# design.net
KiCad netlist of a schematic drawn in EasyEDA Pro
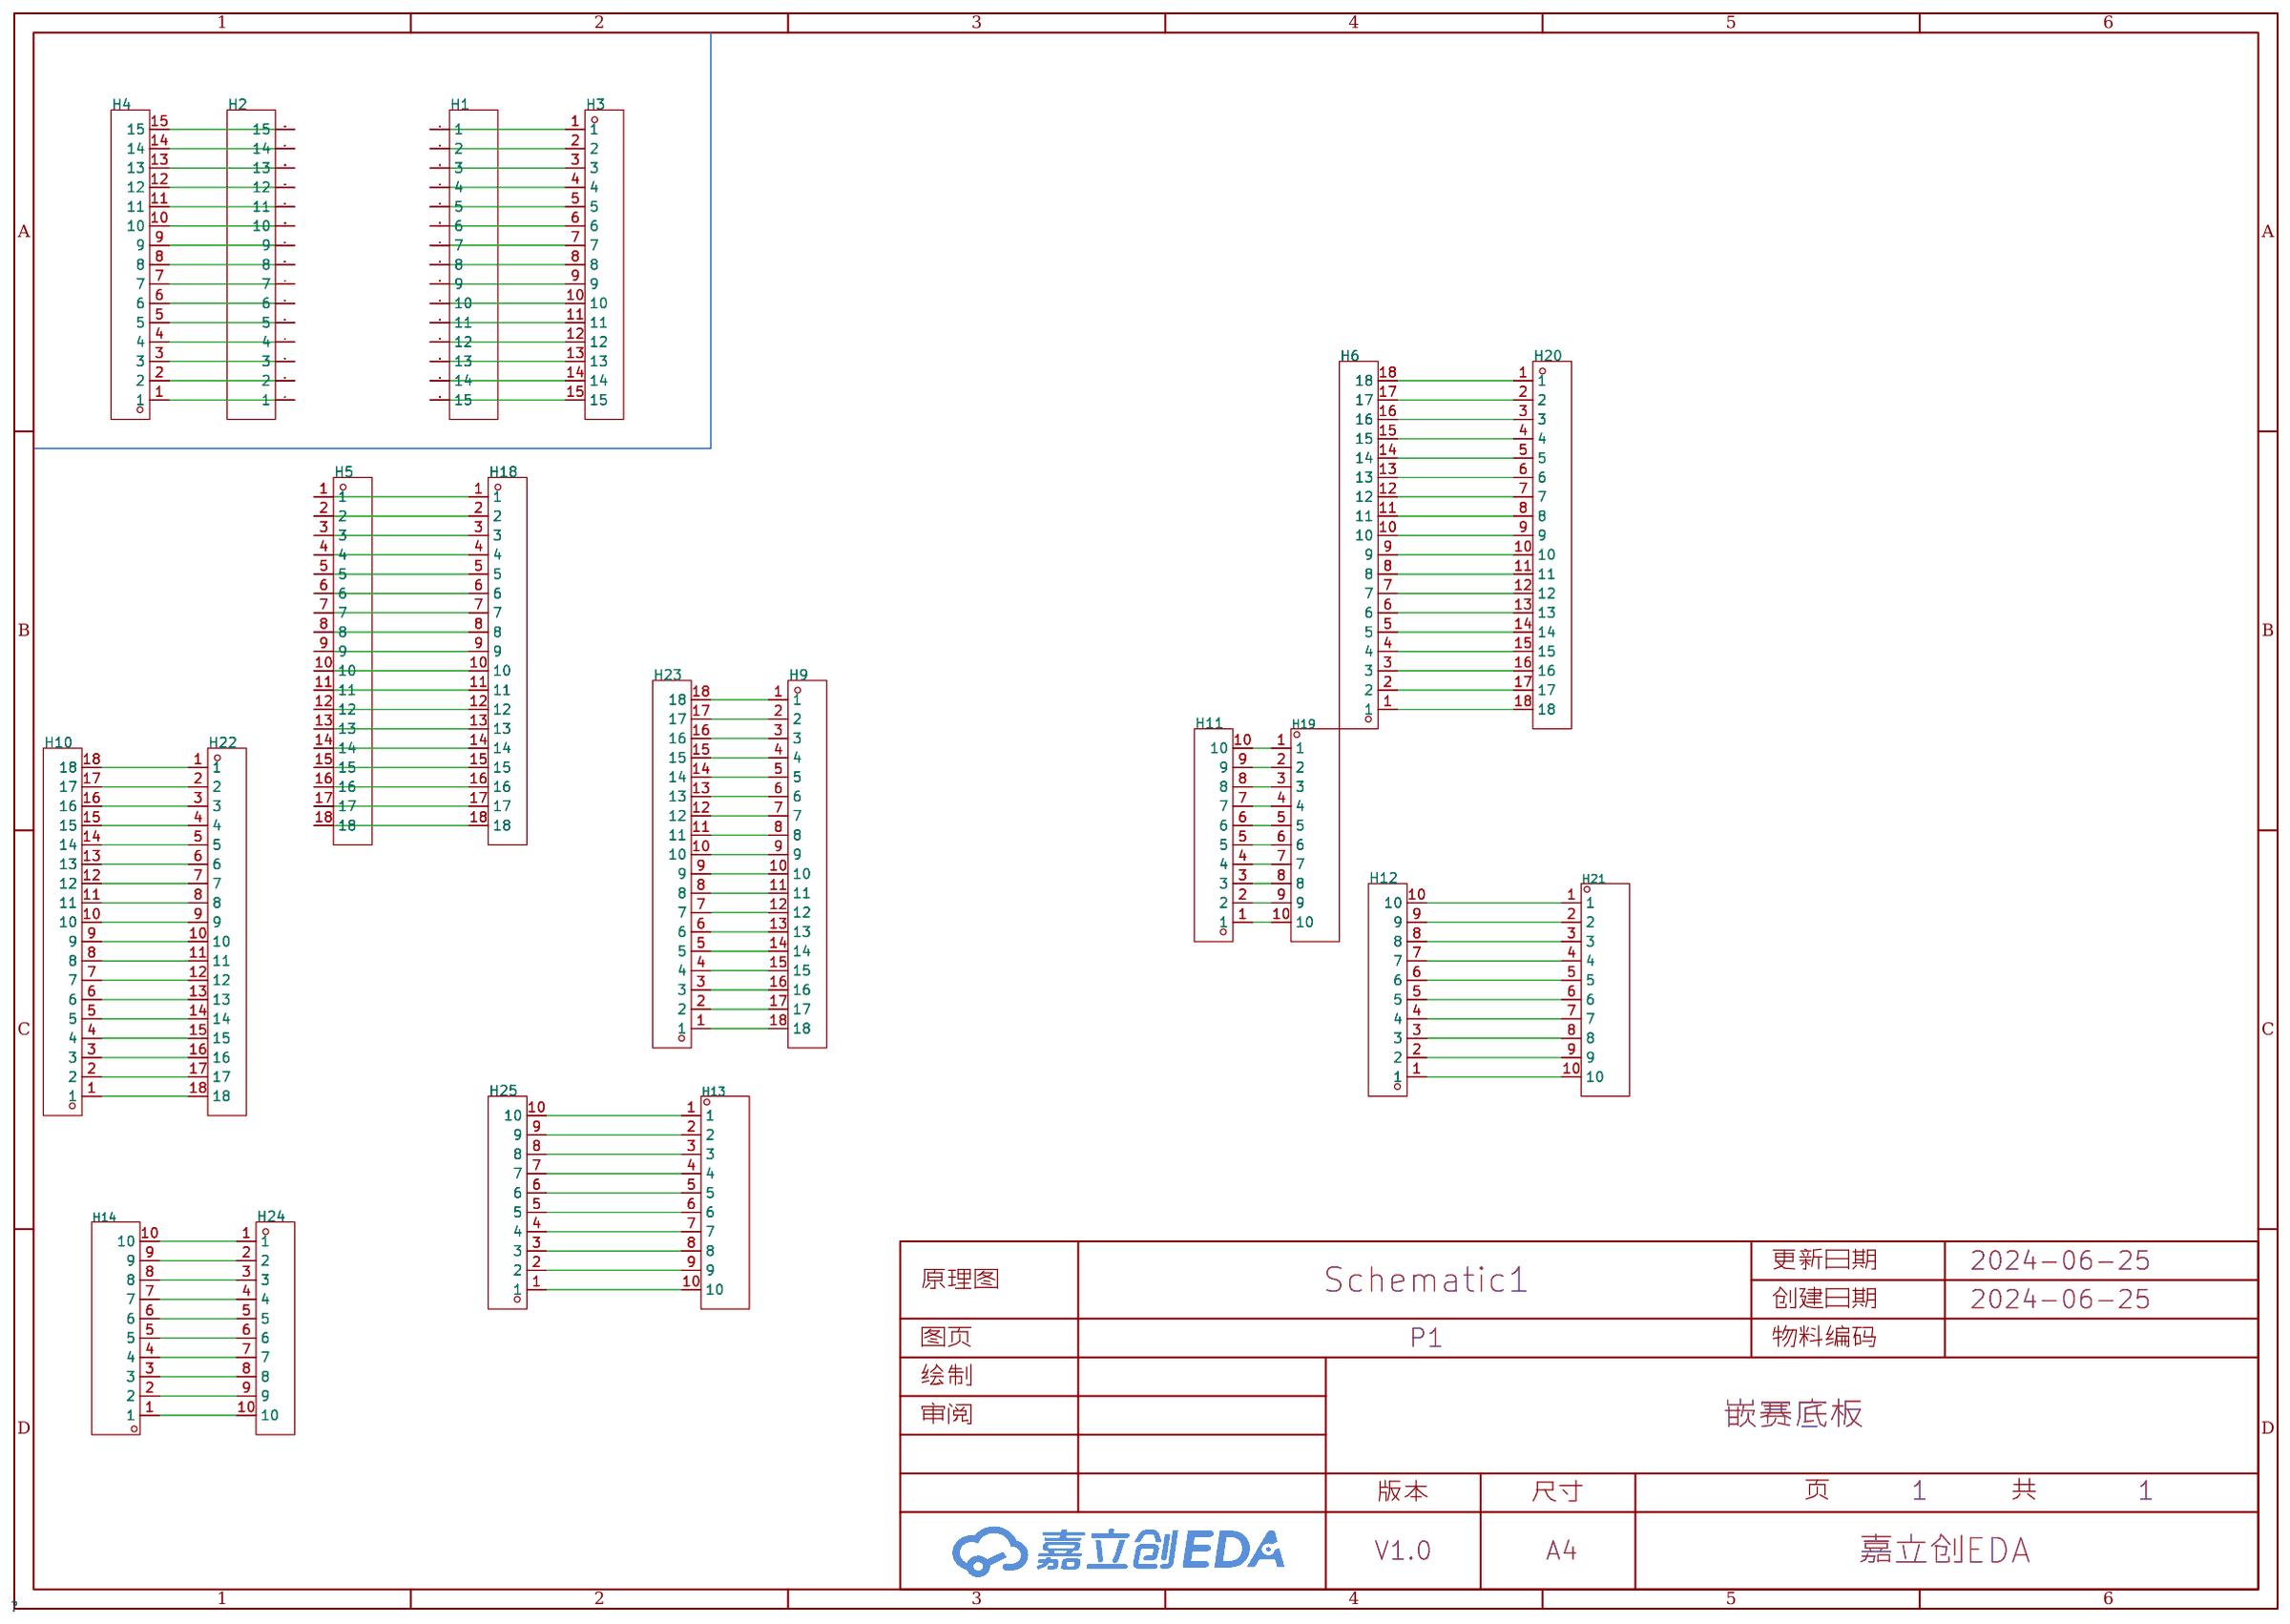
[diagram p0: schematic sheet]

(export (version "E")
  (design (tool "Eeschema 10.0.6"))
  (components
    (comp (ref "H1")
      (value "~")
      (footprint "easyedapro:HDR-TH_15P-P2.54-V-F-1")
      (libsource (lib "easyedapro") (part "HDR-F_2.54_1x15P"))
    )
    (comp (ref "H2")
      (value "~")
      (footprint "easyedapro:HDR-TH_15P-P2.54-V-F-1")
      (libsource (lib "easyedapro") (part "HDR-F_2.54_1x15P"))
    )
    (comp (ref "H3")
      (value "~")
      (footprint "easyedapro:HDR-TH_15P-P2.54-V-M")
      (libsource (lib "easyedapro") (part "HDR_2.54-1x15P"))
    )
    (comp (ref "H4")
      (value "~")
      (footprint "easyedapro:HDR-TH_15P-P2.54-V-M")
      (libsource (lib "easyedapro") (part "HDR_2.54-1x15P"))
    )
    (comp (ref "H5")
      (value "~")
      (footprint "easyedapro:HDR-TH_18P-P2.54-V-F")
      (libsource (lib "easyedapro") (part "HDR-F_2.54_1x18P"))
    )
    (comp (ref "H6")
      (value "~")
      (footprint "easyedapro:HDR-TH_18P-P2.54-V-F")
      (libsource (lib "easyedapro") (part "HDR-F_2.54_1x18P"))
    )
    (comp (ref "H9")
      (value "~")
      (footprint "easyedapro:HDR-TH_18P-P2.54-V-M")
      (libsource (lib "easyedapro") (part "HDR_2.54-1x18P"))
    )
    (comp (ref "H10")
      (value "~")
      (footprint "easyedapro:HDR-TH_18P-P2.54-V-M")
      (libsource (lib "easyedapro") (part "HDR_2.54-1x18P"))
    )
    (comp (ref "H11")
      (value "~")
      (footprint "easyedapro:HDR-TH_10P-P2.54-V-F")
      (libsource (lib "easyedapro") (part "X5511FV-10-C70D30-1000"))
    )
    (comp (ref "H12")
      (value "~")
      (footprint "easyedapro:HDR-TH_10P-P2.54-V-F")
      (libsource (lib "easyedapro") (part "X5511FV-10-C70D30-1000"))
    )
    (comp (ref "H13")
      (value "~")
      (footprint "easyedapro:HDR-TH_10P-P2.54-V-M-1")
      (libsource (lib "easyedapro") (part "Header-Male-2.54_1x10"))
    )
    (comp (ref "H14")
      (value "~")
      (footprint "easyedapro:HDR-TH_10P-P2.54-V-M-1")
      (libsource (lib "easyedapro") (part "Header-Male-2.54_1x10"))
    )
    (comp (ref "H18")
      (value "~")
      (footprint "easyedapro:HDR-TH_18P-P2.54-V-M")
      (libsource (lib "easyedapro") (part "HDR_2.54-1x18P"))
    )
    (comp (ref "H19")
      (value "~")
      (footprint "easyedapro:HDR-TH_10P-P2.54-V-M-1")
      (libsource (lib "easyedapro") (part "Header-Male-2.54_1x10"))
    )
    (comp (ref "H20")
      (value "~")
      (footprint "easyedapro:HDR-TH_18P-P2.54-V-M")
      (libsource (lib "easyedapro") (part "HDR_2.54-1x18P"))
    )
    (comp (ref "H21")
      (value "~")
      (footprint "easyedapro:HDR-TH_10P-P2.54-V-M-1")
      (libsource (lib "easyedapro") (part "Header-Male-2.54_1x10"))
    )
    (comp (ref "H22")
      (value "~")
      (footprint "easyedapro:HDR-TH_18P-P2.54-V-F")
      (libsource (lib "easyedapro") (part "HDR-F_2.54_1x18P"))
    )
    (comp (ref "H23")
      (value "~")
      (footprint "easyedapro:HDR-TH_18P-P2.54-V-F")
      (libsource (lib "easyedapro") (part "HDR-F_2.54_1x18P"))
    )
    (comp (ref "H24")
      (value "~")
      (footprint "easyedapro:HDR-TH_10P-P2.54-V-F")
      (libsource (lib "easyedapro") (part "X5511FV-10-C70D30-1000"))
    )
    (comp (ref "H25")
      (value "~")
      (footprint "easyedapro:HDR-TH_10P-P2.54-V-F")
      (libsource (lib "easyedapro") (part "X5511FV-10-C70D30-1000"))
    )
  )
  (nets
    (net (code "1") (name "Net-(H1-Pad1)") (class "Default")
      (node (ref "H1") (pin "1") (pinfunction "1_1") (pintype "input"))
      (node (ref "H3") (pin "1") (pinfunction "1_1") (pintype "input"))
    )
    (net (code "2") (name "Net-(H1-Pad2)") (class "Default")
      (node (ref "H1") (pin "2") (pinfunction "2_2") (pintype "input"))
      (node (ref "H3") (pin "2") (pinfunction "2_2") (pintype "input"))
    )
    (net (code "3") (name "Net-(H1-Pad3)") (class "Default")
      (node (ref "H1") (pin "3") (pinfunction "3_3") (pintype "input"))
      (node (ref "H3") (pin "3") (pinfunction "3_3") (pintype "input"))
    )
    (net (code "4") (name "Net-(H1-Pad4)") (class "Default")
      (node (ref "H1") (pin "4") (pinfunction "4_4") (pintype "input"))
      (node (ref "H3") (pin "4") (pinfunction "4_4") (pintype "input"))
    )
    (net (code "5") (name "Net-(H1-Pad5)") (class "Default")
      (node (ref "H1") (pin "5") (pinfunction "5_5") (pintype "input"))
      (node (ref "H3") (pin "5") (pinfunction "5_5") (pintype "input"))
    )
    (net (code "6") (name "Net-(H1-Pad6)") (class "Default")
      (node (ref "H1") (pin "6") (pinfunction "6_6") (pintype "input"))
      (node (ref "H3") (pin "6") (pinfunction "6_6") (pintype "input"))
    )
    (net (code "7") (name "Net-(H1-Pad7)") (class "Default")
      (node (ref "H1") (pin "7") (pinfunction "7_7") (pintype "input"))
      (node (ref "H3") (pin "7") (pinfunction "7_7") (pintype "input"))
    )
    (net (code "8") (name "Net-(H1-Pad8)") (class "Default")
      (node (ref "H1") (pin "8") (pinfunction "8_8") (pintype "input"))
      (node (ref "H3") (pin "8") (pinfunction "8_8") (pintype "input"))
    )
    (net (code "9") (name "Net-(H1-Pad9)") (class "Default")
      (node (ref "H1") (pin "9") (pinfunction "9_9") (pintype "input"))
      (node (ref "H3") (pin "9") (pinfunction "9_9") (pintype "input"))
    )
    (net (code "10") (name "Net-(H1-Pad10)") (class "Default")
      (node (ref "H1") (pin "10") (pinfunction "10_10") (pintype "input"))
      (node (ref "H3") (pin "10") (pinfunction "10_10") (pintype "input"))
    )
    (net (code "11") (name "Net-(H1-Pad11)") (class "Default")
      (node (ref "H1") (pin "11") (pinfunction "11_11") (pintype "input"))
      (node (ref "H3") (pin "11") (pinfunction "11_11") (pintype "input"))
    )
    (net (code "12") (name "Net-(H1-Pad12)") (class "Default")
      (node (ref "H1") (pin "12") (pinfunction "12_12") (pintype "input"))
      (node (ref "H3") (pin "12") (pinfunction "12_12") (pintype "input"))
    )
    (net (code "13") (name "Net-(H1-Pad13)") (class "Default")
      (node (ref "H1") (pin "13") (pinfunction "13_13") (pintype "input"))
      (node (ref "H3") (pin "13") (pinfunction "13_13") (pintype "input"))
    )
    (net (code "14") (name "Net-(H1-Pad14)") (class "Default")
      (node (ref "H1") (pin "14") (pinfunction "14_14") (pintype "input"))
      (node (ref "H3") (pin "14") (pinfunction "14_14") (pintype "input"))
    )
    (net (code "15") (name "Net-(H1-Pad15)") (class "Default")
      (node (ref "H1") (pin "15") (pinfunction "15_15") (pintype "input"))
      (node (ref "H3") (pin "15") (pinfunction "15_15") (pintype "input"))
    )
    (net (code "16") (name "Net-(H2-Pad1)") (class "Default")
      (node (ref "H2") (pin "1") (pinfunction "1_1") (pintype "input"))
      (node (ref "H4") (pin "1") (pinfunction "1_1") (pintype "input"))
    )
    (net (code "17") (name "Net-(H2-Pad2)") (class "Default")
      (node (ref "H2") (pin "2") (pinfunction "2_2") (pintype "input"))
      (node (ref "H4") (pin "2") (pinfunction "2_2") (pintype "input"))
    )
    (net (code "18") (name "Net-(H2-Pad3)") (class "Default")
      (node (ref "H2") (pin "3") (pinfunction "3_3") (pintype "input"))
      (node (ref "H4") (pin "3") (pinfunction "3_3") (pintype "input"))
    )
    (net (code "19") (name "Net-(H2-Pad4)") (class "Default")
      (node (ref "H2") (pin "4") (pinfunction "4_4") (pintype "input"))
      (node (ref "H4") (pin "4") (pinfunction "4_4") (pintype "input"))
    )
    (net (code "20") (name "Net-(H2-Pad5)") (class "Default")
      (node (ref "H2") (pin "5") (pinfunction "5_5") (pintype "input"))
      (node (ref "H4") (pin "5") (pinfunction "5_5") (pintype "input"))
    )
    (net (code "21") (name "Net-(H2-Pad6)") (class "Default")
      (node (ref "H2") (pin "6") (pinfunction "6_6") (pintype "input"))
      (node (ref "H4") (pin "6") (pinfunction "6_6") (pintype "input"))
    )
    (net (code "22") (name "Net-(H2-Pad7)") (class "Default")
      (node (ref "H2") (pin "7") (pinfunction "7_7") (pintype "input"))
      (node (ref "H4") (pin "7") (pinfunction "7_7") (pintype "input"))
    )
    (net (code "23") (name "Net-(H2-Pad8)") (class "Default")
      (node (ref "H2") (pin "8") (pinfunction "8_8") (pintype "input"))
      (node (ref "H4") (pin "8") (pinfunction "8_8") (pintype "input"))
    )
    (net (code "24") (name "Net-(H2-Pad9)") (class "Default")
      (node (ref "H2") (pin "9") (pinfunction "9_9") (pintype "input"))
      (node (ref "H4") (pin "9") (pinfunction "9_9") (pintype "input"))
    )
    (net (code "25") (name "Net-(H2-Pad10)") (class "Default")
      (node (ref "H2") (pin "10") (pinfunction "10_10") (pintype "input"))
      (node (ref "H4") (pin "10") (pinfunction "10_10") (pintype "input"))
    )
    (net (code "26") (name "Net-(H2-Pad11)") (class "Default")
      (node (ref "H2") (pin "11") (pinfunction "11_11") (pintype "input"))
      (node (ref "H4") (pin "11") (pinfunction "11_11") (pintype "input"))
    )
    (net (code "27") (name "Net-(H2-Pad12)") (class "Default")
      (node (ref "H2") (pin "12") (pinfunction "12_12") (pintype "input"))
      (node (ref "H4") (pin "12") (pinfunction "12_12") (pintype "input"))
    )
    (net (code "28") (name "Net-(H2-Pad13)") (class "Default")
      (node (ref "H2") (pin "13") (pinfunction "13_13") (pintype "input"))
      (node (ref "H4") (pin "13") (pinfunction "13_13") (pintype "input"))
    )
    (net (code "29") (name "Net-(H2-Pad14)") (class "Default")
      (node (ref "H2") (pin "14") (pinfunction "14_14") (pintype "input"))
      (node (ref "H4") (pin "14") (pinfunction "14_14") (pintype "input"))
    )
    (net (code "30") (name "Net-(H2-Pad15)") (class "Default")
      (node (ref "H2") (pin "15") (pinfunction "15_15") (pintype "input"))
      (node (ref "H4") (pin "15") (pinfunction "15_15") (pintype "input"))
    )
    (net (code "31") (name "Net-(H10-Pad1)") (class "Default")
      (node (ref "H10") (pin "1") (pinfunction "1_1") (pintype "input"))
      (node (ref "H22") (pin "18") (pinfunction "18_18") (pintype "input"))
    )
    (net (code "32") (name "Net-(H10-Pad2)") (class "Default")
      (node (ref "H10") (pin "2") (pinfunction "2_2") (pintype "input"))
      (node (ref "H22") (pin "17") (pinfunction "17_17") (pintype "input"))
    )
    (net (code "33") (name "Net-(H10-Pad3)") (class "Default")
      (node (ref "H10") (pin "3") (pinfunction "3_3") (pintype "input"))
      (node (ref "H22") (pin "16") (pinfunction "16_16") (pintype "input"))
    )
    (net (code "34") (name "Net-(H10-Pad4)") (class "Default")
      (node (ref "H10") (pin "4") (pinfunction "4_4") (pintype "input"))
      (node (ref "H22") (pin "15") (pinfunction "15_15") (pintype "input"))
    )
    (net (code "35") (name "Net-(H10-Pad5)") (class "Default")
      (node (ref "H10") (pin "5") (pinfunction "5_5") (pintype "input"))
      (node (ref "H22") (pin "14") (pinfunction "14_14") (pintype "input"))
    )
    (net (code "36") (name "Net-(H10-Pad6)") (class "Default")
      (node (ref "H10") (pin "6") (pinfunction "6_6") (pintype "input"))
      (node (ref "H22") (pin "13") (pinfunction "13_13") (pintype "input"))
    )
    (net (code "37") (name "Net-(H10-Pad7)") (class "Default")
      (node (ref "H10") (pin "7") (pinfunction "7_7") (pintype "input"))
      (node (ref "H22") (pin "12") (pinfunction "12_12") (pintype "input"))
    )
    (net (code "38") (name "Net-(H10-Pad8)") (class "Default")
      (node (ref "H10") (pin "8") (pinfunction "8_8") (pintype "input"))
      (node (ref "H22") (pin "11") (pinfunction "11_11") (pintype "input"))
    )
    (net (code "39") (name "Net-(H10-Pad9)") (class "Default")
      (node (ref "H10") (pin "9") (pinfunction "9_9") (pintype "input"))
      (node (ref "H22") (pin "10") (pinfunction "10_10") (pintype "input"))
    )
    (net (code "40") (name "Net-(H10-Pad10)") (class "Default")
      (node (ref "H10") (pin "10") (pinfunction "10_10") (pintype "input"))
      (node (ref "H22") (pin "9") (pinfunction "9_9") (pintype "input"))
    )
    (net (code "41") (name "Net-(H10-Pad11)") (class "Default")
      (node (ref "H10") (pin "11") (pinfunction "11_11") (pintype "input"))
      (node (ref "H22") (pin "8") (pinfunction "8_8") (pintype "input"))
    )
    (net (code "42") (name "Net-(H10-Pad12)") (class "Default")
      (node (ref "H10") (pin "12") (pinfunction "12_12") (pintype "input"))
      (node (ref "H22") (pin "7") (pinfunction "7_7") (pintype "input"))
    )
    (net (code "43") (name "Net-(H10-Pad13)") (class "Default")
      (node (ref "H10") (pin "13") (pinfunction "13_13") (pintype "input"))
      (node (ref "H22") (pin "6") (pinfunction "6_6") (pintype "input"))
    )
    (net (code "44") (name "Net-(H10-Pad14)") (class "Default")
      (node (ref "H10") (pin "14") (pinfunction "14_14") (pintype "input"))
      (node (ref "H22") (pin "5") (pinfunction "5_5") (pintype "input"))
    )
    (net (code "45") (name "Net-(H10-Pad15)") (class "Default")
      (node (ref "H10") (pin "15") (pinfunction "15_15") (pintype "input"))
      (node (ref "H22") (pin "4") (pinfunction "4_4") (pintype "input"))
    )
    (net (code "46") (name "Net-(H10-Pad16)") (class "Default")
      (node (ref "H10") (pin "16") (pinfunction "16_16") (pintype "input"))
      (node (ref "H22") (pin "3") (pinfunction "3_3") (pintype "input"))
    )
    (net (code "47") (name "Net-(H10-Pad17)") (class "Default")
      (node (ref "H10") (pin "17") (pinfunction "17_17") (pintype "input"))
      (node (ref "H22") (pin "2") (pinfunction "2_2") (pintype "input"))
    )
    (net (code "48") (name "Net-(H10-Pad18)") (class "Default")
      (node (ref "H10") (pin "18") (pinfunction "18_18") (pintype "input"))
      (node (ref "H22") (pin "1") (pinfunction "1_1") (pintype "input"))
    )
    (net (code "49") (name "Net-(H11-Pad1)") (class "Default")
      (node (ref "H11") (pin "1") (pinfunction "1_1") (pintype "unspecified"))
      (node (ref "H19") (pin "10") (pinfunction "10_10") (pintype "input"))
    )
    (net (code "50") (name "Net-(H11-Pad2)") (class "Default")
      (node (ref "H11") (pin "2") (pinfunction "2_2") (pintype "unspecified"))
      (node (ref "H19") (pin "9") (pinfunction "9_9") (pintype "input"))
    )
    (net (code "51") (name "Net-(H11-Pad3)") (class "Default")
      (node (ref "H11") (pin "3") (pinfunction "3_3") (pintype "unspecified"))
      (node (ref "H19") (pin "8") (pinfunction "8_8") (pintype "input"))
    )
    (net (code "52") (name "Net-(H11-Pad4)") (class "Default")
      (node (ref "H11") (pin "4") (pinfunction "4_4") (pintype "unspecified"))
      (node (ref "H19") (pin "7") (pinfunction "7_7") (pintype "input"))
    )
    (net (code "53") (name "Net-(H11-Pad5)") (class "Default")
      (node (ref "H11") (pin "5") (pinfunction "5_5") (pintype "unspecified"))
      (node (ref "H19") (pin "6") (pinfunction "6_6") (pintype "input"))
    )
    (net (code "54") (name "Net-(H11-Pad6)") (class "Default")
      (node (ref "H11") (pin "6") (pinfunction "6_6") (pintype "unspecified"))
      (node (ref "H19") (pin "5") (pinfunction "5_5") (pintype "input"))
    )
    (net (code "55") (name "Net-(H11-Pad7)") (class "Default")
      (node (ref "H11") (pin "7") (pinfunction "7_7") (pintype "unspecified"))
      (node (ref "H19") (pin "4") (pinfunction "4_4") (pintype "input"))
    )
    (net (code "56") (name "Net-(H11-Pad8)") (class "Default")
      (node (ref "H11") (pin "8") (pinfunction "8_8") (pintype "unspecified"))
      (node (ref "H19") (pin "3") (pinfunction "3_3") (pintype "input"))
    )
    (net (code "57") (name "Net-(H11-Pad9)") (class "Default")
      (node (ref "H11") (pin "9") (pinfunction "9_9") (pintype "unspecified"))
      (node (ref "H19") (pin "2") (pinfunction "2_2") (pintype "input"))
    )
    (net (code "58") (name "Net-(H11-Pad10)") (class "Default")
      (node (ref "H11") (pin "10") (pinfunction "10_10") (pintype "unspecified"))
      (node (ref "H19") (pin "1") (pinfunction "1_1") (pintype "input"))
    )
    (net (code "59") (name "Net-(H12-Pad1)") (class "Default")
      (node (ref "H12") (pin "1") (pinfunction "1_1") (pintype "unspecified"))
      (node (ref "H21") (pin "10") (pinfunction "10_10") (pintype "input"))
    )
    (net (code "60") (name "Net-(H12-Pad2)") (class "Default")
      (node (ref "H12") (pin "2") (pinfunction "2_2") (pintype "unspecified"))
      (node (ref "H21") (pin "9") (pinfunction "9_9") (pintype "input"))
    )
    (net (code "61") (name "Net-(H12-Pad3)") (class "Default")
      (node (ref "H12") (pin "3") (pinfunction "3_3") (pintype "unspecified"))
      (node (ref "H21") (pin "8") (pinfunction "8_8") (pintype "input"))
    )
    (net (code "62") (name "Net-(H12-Pad4)") (class "Default")
      (node (ref "H12") (pin "4") (pinfunction "4_4") (pintype "unspecified"))
      (node (ref "H21") (pin "7") (pinfunction "7_7") (pintype "input"))
    )
    (net (code "63") (name "Net-(H12-Pad5)") (class "Default")
      (node (ref "H12") (pin "5") (pinfunction "5_5") (pintype "unspecified"))
      (node (ref "H21") (pin "6") (pinfunction "6_6") (pintype "input"))
    )
    (net (code "64") (name "Net-(H12-Pad6)") (class "Default")
      (node (ref "H12") (pin "6") (pinfunction "6_6") (pintype "unspecified"))
      (node (ref "H21") (pin "5") (pinfunction "5_5") (pintype "input"))
    )
    (net (code "65") (name "Net-(H12-Pad7)") (class "Default")
      (node (ref "H12") (pin "7") (pinfunction "7_7") (pintype "unspecified"))
      (node (ref "H21") (pin "4") (pinfunction "4_4") (pintype "input"))
    )
    (net (code "66") (name "Net-(H12-Pad8)") (class "Default")
      (node (ref "H12") (pin "8") (pinfunction "8_8") (pintype "unspecified"))
      (node (ref "H21") (pin "3") (pinfunction "3_3") (pintype "input"))
    )
    (net (code "67") (name "Net-(H12-Pad9)") (class "Default")
      (node (ref "H12") (pin "9") (pinfunction "9_9") (pintype "unspecified"))
      (node (ref "H21") (pin "2") (pinfunction "2_2") (pintype "input"))
    )
    (net (code "68") (name "Net-(H12-Pad10)") (class "Default")
      (node (ref "H12") (pin "10") (pinfunction "10_10") (pintype "unspecified"))
      (node (ref "H21") (pin "1") (pinfunction "1_1") (pintype "input"))
    )
    (net (code "69") (name "Net-(H13-Pad1)") (class "Default")
      (node (ref "H13") (pin "1") (pinfunction "1_1") (pintype "input"))
      (node (ref "H25") (pin "10") (pinfunction "10_10") (pintype "unspecified"))
    )
    (net (code "70") (name "Net-(H13-Pad2)") (class "Default")
      (node (ref "H13") (pin "2") (pinfunction "2_2") (pintype "input"))
      (node (ref "H25") (pin "9") (pinfunction "9_9") (pintype "unspecified"))
    )
    (net (code "71") (name "Net-(H13-Pad3)") (class "Default")
      (node (ref "H13") (pin "3") (pinfunction "3_3") (pintype "input"))
      (node (ref "H25") (pin "8") (pinfunction "8_8") (pintype "unspecified"))
    )
    (net (code "72") (name "Net-(H13-Pad4)") (class "Default")
      (node (ref "H13") (pin "4") (pinfunction "4_4") (pintype "input"))
      (node (ref "H25") (pin "7") (pinfunction "7_7") (pintype "unspecified"))
    )
    (net (code "73") (name "Net-(H13-Pad5)") (class "Default")
      (node (ref "H13") (pin "5") (pinfunction "5_5") (pintype "input"))
      (node (ref "H25") (pin "6") (pinfunction "6_6") (pintype "unspecified"))
    )
    (net (code "74") (name "Net-(H13-Pad6)") (class "Default")
      (node (ref "H13") (pin "6") (pinfunction "6_6") (pintype "input"))
      (node (ref "H25") (pin "5") (pinfunction "5_5") (pintype "unspecified"))
    )
    (net (code "75") (name "Net-(H13-Pad7)") (class "Default")
      (node (ref "H13") (pin "7") (pinfunction "7_7") (pintype "input"))
      (node (ref "H25") (pin "4") (pinfunction "4_4") (pintype "unspecified"))
    )
    (net (code "76") (name "Net-(H13-Pad8)") (class "Default")
      (node (ref "H13") (pin "8") (pinfunction "8_8") (pintype "input"))
      (node (ref "H25") (pin "3") (pinfunction "3_3") (pintype "unspecified"))
    )
    (net (code "77") (name "Net-(H13-Pad9)") (class "Default")
      (node (ref "H13") (pin "9") (pinfunction "9_9") (pintype "input"))
      (node (ref "H25") (pin "2") (pinfunction "2_2") (pintype "unspecified"))
    )
    (net (code "78") (name "Net-(H13-Pad10)") (class "Default")
      (node (ref "H13") (pin "10") (pinfunction "10_10") (pintype "input"))
      (node (ref "H25") (pin "1") (pinfunction "1_1") (pintype "unspecified"))
    )
    (net (code "79") (name "Net-(H14-Pad1)") (class "Default")
      (node (ref "H14") (pin "1") (pinfunction "1_1") (pintype "input"))
      (node (ref "H24") (pin "10") (pinfunction "10_10") (pintype "unspecified"))
    )
    (net (code "80") (name "Net-(H14-Pad2)") (class "Default")
      (node (ref "H14") (pin "2") (pinfunction "2_2") (pintype "input"))
      (node (ref "H24") (pin "9") (pinfunction "9_9") (pintype "unspecified"))
    )
    (net (code "81") (name "Net-(H14-Pad3)") (class "Default")
      (node (ref "H14") (pin "3") (pinfunction "3_3") (pintype "input"))
      (node (ref "H24") (pin "8") (pinfunction "8_8") (pintype "unspecified"))
    )
    (net (code "82") (name "Net-(H14-Pad4)") (class "Default")
      (node (ref "H14") (pin "4") (pinfunction "4_4") (pintype "input"))
      (node (ref "H24") (pin "7") (pinfunction "7_7") (pintype "unspecified"))
    )
    (net (code "83") (name "Net-(H14-Pad5)") (class "Default")
      (node (ref "H14") (pin "5") (pinfunction "5_5") (pintype "input"))
      (node (ref "H24") (pin "6") (pinfunction "6_6") (pintype "unspecified"))
    )
    (net (code "84") (name "Net-(H14-Pad6)") (class "Default")
      (node (ref "H14") (pin "6") (pinfunction "6_6") (pintype "input"))
      (node (ref "H24") (pin "5") (pinfunction "5_5") (pintype "unspecified"))
    )
    (net (code "85") (name "Net-(H14-Pad7)") (class "Default")
      (node (ref "H14") (pin "7") (pinfunction "7_7") (pintype "input"))
      (node (ref "H24") (pin "4") (pinfunction "4_4") (pintype "unspecified"))
    )
    (net (code "86") (name "Net-(H14-Pad8)") (class "Default")
      (node (ref "H14") (pin "8") (pinfunction "8_8") (pintype "input"))
      (node (ref "H24") (pin "3") (pinfunction "3_3") (pintype "unspecified"))
    )
    (net (code "87") (name "Net-(H14-Pad9)") (class "Default")
      (node (ref "H14") (pin "9") (pinfunction "9_9") (pintype "input"))
      (node (ref "H24") (pin "2") (pinfunction "2_2") (pintype "unspecified"))
    )
    (net (code "88") (name "Net-(H14-Pad10)") (class "Default")
      (node (ref "H14") (pin "10") (pinfunction "10_10") (pintype "input"))
      (node (ref "H24") (pin "1") (pinfunction "1_1") (pintype "unspecified"))
    )
    (net (code "89") (name "Net-(H18-Pad1)") (class "Default")
      (node (ref "H18") (pin "1") (pinfunction "1_1") (pintype "input"))
      (node (ref "H5") (pin "1") (pinfunction "1_1") (pintype "input"))
    )
    (net (code "90") (name "Net-(H18-Pad2)") (class "Default")
      (node (ref "H18") (pin "2") (pinfunction "2_2") (pintype "input"))
      (node (ref "H5") (pin "2") (pinfunction "2_2") (pintype "input"))
    )
    (net (code "91") (name "Net-(H18-Pad3)") (class "Default")
      (node (ref "H18") (pin "3") (pinfunction "3_3") (pintype "input"))
      (node (ref "H5") (pin "3") (pinfunction "3_3") (pintype "input"))
    )
    (net (code "92") (name "Net-(H18-Pad4)") (class "Default")
      (node (ref "H18") (pin "4") (pinfunction "4_4") (pintype "input"))
      (node (ref "H5") (pin "4") (pinfunction "4_4") (pintype "input"))
    )
    (net (code "93") (name "Net-(H18-Pad5)") (class "Default")
      (node (ref "H18") (pin "5") (pinfunction "5_5") (pintype "input"))
      (node (ref "H5") (pin "5") (pinfunction "5_5") (pintype "input"))
    )
    (net (code "94") (name "Net-(H18-Pad6)") (class "Default")
      (node (ref "H18") (pin "6") (pinfunction "6_6") (pintype "input"))
      (node (ref "H5") (pin "6") (pinfunction "6_6") (pintype "input"))
    )
    (net (code "95") (name "Net-(H18-Pad7)") (class "Default")
      (node (ref "H18") (pin "7") (pinfunction "7_7") (pintype "input"))
      (node (ref "H5") (pin "7") (pinfunction "7_7") (pintype "input"))
    )
    (net (code "96") (name "Net-(H18-Pad8)") (class "Default")
      (node (ref "H18") (pin "8") (pinfunction "8_8") (pintype "input"))
      (node (ref "H5") (pin "8") (pinfunction "8_8") (pintype "input"))
    )
    (net (code "97") (name "Net-(H18-Pad9)") (class "Default")
      (node (ref "H18") (pin "9") (pinfunction "9_9") (pintype "input"))
      (node (ref "H5") (pin "9") (pinfunction "9_9") (pintype "input"))
    )
    (net (code "98") (name "Net-(H18-Pad10)") (class "Default")
      (node (ref "H18") (pin "10") (pinfunction "10_10") (pintype "input"))
      (node (ref "H5") (pin "10") (pinfunction "10_10") (pintype "input"))
    )
    (net (code "99") (name "Net-(H18-Pad11)") (class "Default")
      (node (ref "H18") (pin "11") (pinfunction "11_11") (pintype "input"))
      (node (ref "H5") (pin "11") (pinfunction "11_11") (pintype "input"))
    )
    (net (code "100") (name "Net-(H18-Pad12)") (class "Default")
      (node (ref "H18") (pin "12") (pinfunction "12_12") (pintype "input"))
      (node (ref "H5") (pin "12") (pinfunction "12_12") (pintype "input"))
    )
    (net (code "101") (name "Net-(H18-Pad13)") (class "Default")
      (node (ref "H18") (pin "13") (pinfunction "13_13") (pintype "input"))
      (node (ref "H5") (pin "13") (pinfunction "13_13") (pintype "input"))
    )
    (net (code "102") (name "Net-(H18-Pad14)") (class "Default")
      (node (ref "H18") (pin "14") (pinfunction "14_14") (pintype "input"))
      (node (ref "H5") (pin "14") (pinfunction "14_14") (pintype "input"))
    )
    (net (code "103") (name "Net-(H18-Pad15)") (class "Default")
      (node (ref "H18") (pin "15") (pinfunction "15_15") (pintype "input"))
      (node (ref "H5") (pin "15") (pinfunction "15_15") (pintype "input"))
    )
    (net (code "104") (name "Net-(H18-Pad16)") (class "Default")
      (node (ref "H18") (pin "16") (pinfunction "16_16") (pintype "input"))
      (node (ref "H5") (pin "16") (pinfunction "16_16") (pintype "input"))
    )
    (net (code "105") (name "Net-(H18-Pad17)") (class "Default")
      (node (ref "H18") (pin "17") (pinfunction "17_17") (pintype "input"))
      (node (ref "H5") (pin "17") (pinfunction "17_17") (pintype "input"))
    )
    (net (code "106") (name "Net-(H18-Pad18)") (class "Default")
      (node (ref "H18") (pin "18") (pinfunction "18_18") (pintype "input"))
      (node (ref "H5") (pin "18") (pinfunction "18_18") (pintype "input"))
    )
    (net (code "107") (name "Net-(H20-Pad1)") (class "Default")
      (node (ref "H20") (pin "1") (pinfunction "1_1") (pintype "input"))
      (node (ref "H6") (pin "18") (pinfunction "18_18") (pintype "input"))
    )
    (net (code "108") (name "Net-(H20-Pad2)") (class "Default")
      (node (ref "H20") (pin "2") (pinfunction "2_2") (pintype "input"))
      (node (ref "H6") (pin "17") (pinfunction "17_17") (pintype "input"))
    )
    (net (code "109") (name "Net-(H20-Pad3)") (class "Default")
      (node (ref "H20") (pin "3") (pinfunction "3_3") (pintype "input"))
      (node (ref "H6") (pin "16") (pinfunction "16_16") (pintype "input"))
    )
    (net (code "110") (name "Net-(H20-Pad4)") (class "Default")
      (node (ref "H20") (pin "4") (pinfunction "4_4") (pintype "input"))
      (node (ref "H6") (pin "15") (pinfunction "15_15") (pintype "input"))
    )
    (net (code "111") (name "Net-(H20-Pad5)") (class "Default")
      (node (ref "H20") (pin "5") (pinfunction "5_5") (pintype "input"))
      (node (ref "H6") (pin "14") (pinfunction "14_14") (pintype "input"))
    )
    (net (code "112") (name "Net-(H20-Pad6)") (class "Default")
      (node (ref "H20") (pin "6") (pinfunction "6_6") (pintype "input"))
      (node (ref "H6") (pin "13") (pinfunction "13_13") (pintype "input"))
    )
    (net (code "113") (name "Net-(H20-Pad7)") (class "Default")
      (node (ref "H20") (pin "7") (pinfunction "7_7") (pintype "input"))
      (node (ref "H6") (pin "12") (pinfunction "12_12") (pintype "input"))
    )
    (net (code "114") (name "Net-(H20-Pad8)") (class "Default")
      (node (ref "H20") (pin "8") (pinfunction "8_8") (pintype "input"))
      (node (ref "H6") (pin "11") (pinfunction "11_11") (pintype "input"))
    )
    (net (code "115") (name "Net-(H20-Pad9)") (class "Default")
      (node (ref "H20") (pin "9") (pinfunction "9_9") (pintype "input"))
      (node (ref "H6") (pin "10") (pinfunction "10_10") (pintype "input"))
    )
    (net (code "116") (name "Net-(H20-Pad10)") (class "Default")
      (node (ref "H20") (pin "10") (pinfunction "10_10") (pintype "input"))
      (node (ref "H6") (pin "9") (pinfunction "9_9") (pintype "input"))
    )
    (net (code "117") (name "Net-(H20-Pad11)") (class "Default")
      (node (ref "H20") (pin "11") (pinfunction "11_11") (pintype "input"))
      (node (ref "H6") (pin "8") (pinfunction "8_8") (pintype "input"))
    )
    (net (code "118") (name "Net-(H20-Pad12)") (class "Default")
      (node (ref "H20") (pin "12") (pinfunction "12_12") (pintype "input"))
      (node (ref "H6") (pin "7") (pinfunction "7_7") (pintype "input"))
    )
    (net (code "119") (name "Net-(H20-Pad13)") (class "Default")
      (node (ref "H20") (pin "13") (pinfunction "13_13") (pintype "input"))
      (node (ref "H6") (pin "6") (pinfunction "6_6") (pintype "input"))
    )
    (net (code "120") (name "Net-(H20-Pad14)") (class "Default")
      (node (ref "H20") (pin "14") (pinfunction "14_14") (pintype "input"))
      (node (ref "H6") (pin "5") (pinfunction "5_5") (pintype "input"))
    )
    (net (code "121") (name "Net-(H20-Pad15)") (class "Default")
      (node (ref "H20") (pin "15") (pinfunction "15_15") (pintype "input"))
      (node (ref "H6") (pin "4") (pinfunction "4_4") (pintype "input"))
    )
    (net (code "122") (name "Net-(H20-Pad16)") (class "Default")
      (node (ref "H20") (pin "16") (pinfunction "16_16") (pintype "input"))
      (node (ref "H6") (pin "3") (pinfunction "3_3") (pintype "input"))
    )
    (net (code "123") (name "Net-(H20-Pad17)") (class "Default")
      (node (ref "H20") (pin "17") (pinfunction "17_17") (pintype "input"))
      (node (ref "H6") (pin "2") (pinfunction "2_2") (pintype "input"))
    )
    (net (code "124") (name "Net-(H20-Pad18)") (class "Default")
      (node (ref "H20") (pin "18") (pinfunction "18_18") (pintype "input"))
      (node (ref "H6") (pin "1") (pinfunction "1_1") (pintype "input"))
    )
    (net (code "125") (name "Net-(H23-Pad1)") (class "Default")
      (node (ref "H23") (pin "1") (pinfunction "1_1") (pintype "input"))
      (node (ref "H9") (pin "18") (pinfunction "18_18") (pintype "input"))
    )
    (net (code "126") (name "Net-(H23-Pad2)") (class "Default")
      (node (ref "H23") (pin "2") (pinfunction "2_2") (pintype "input"))
      (node (ref "H9") (pin "17") (pinfunction "17_17") (pintype "input"))
    )
    (net (code "127") (name "Net-(H23-Pad3)") (class "Default")
      (node (ref "H23") (pin "3") (pinfunction "3_3") (pintype "input"))
      (node (ref "H9") (pin "16") (pinfunction "16_16") (pintype "input"))
    )
    (net (code "128") (name "Net-(H23-Pad4)") (class "Default")
      (node (ref "H23") (pin "4") (pinfunction "4_4") (pintype "input"))
      (node (ref "H9") (pin "15") (pinfunction "15_15") (pintype "input"))
    )
    (net (code "129") (name "Net-(H23-Pad5)") (class "Default")
      (node (ref "H23") (pin "5") (pinfunction "5_5") (pintype "input"))
      (node (ref "H9") (pin "14") (pinfunction "14_14") (pintype "input"))
    )
    (net (code "130") (name "Net-(H23-Pad6)") (class "Default")
      (node (ref "H23") (pin "6") (pinfunction "6_6") (pintype "input"))
      (node (ref "H9") (pin "13") (pinfunction "13_13") (pintype "input"))
    )
    (net (code "131") (name "Net-(H23-Pad7)") (class "Default")
      (node (ref "H23") (pin "7") (pinfunction "7_7") (pintype "input"))
      (node (ref "H9") (pin "12") (pinfunction "12_12") (pintype "input"))
    )
    (net (code "132") (name "Net-(H23-Pad8)") (class "Default")
      (node (ref "H23") (pin "8") (pinfunction "8_8") (pintype "input"))
      (node (ref "H9") (pin "11") (pinfunction "11_11") (pintype "input"))
    )
    (net (code "133") (name "Net-(H23-Pad9)") (class "Default")
      (node (ref "H23") (pin "9") (pinfunction "9_9") (pintype "input"))
      (node (ref "H9") (pin "10") (pinfunction "10_10") (pintype "input"))
    )
    (net (code "134") (name "Net-(H23-Pad10)") (class "Default")
      (node (ref "H23") (pin "10") (pinfunction "10_10") (pintype "input"))
      (node (ref "H9") (pin "9") (pinfunction "9_9") (pintype "input"))
    )
    (net (code "135") (name "Net-(H23-Pad11)") (class "Default")
      (node (ref "H23") (pin "11") (pinfunction "11_11") (pintype "input"))
      (node (ref "H9") (pin "8") (pinfunction "8_8") (pintype "input"))
    )
    (net (code "136") (name "Net-(H23-Pad12)") (class "Default")
      (node (ref "H23") (pin "12") (pinfunction "12_12") (pintype "input"))
      (node (ref "H9") (pin "7") (pinfunction "7_7") (pintype "input"))
    )
    (net (code "137") (name "Net-(H23-Pad13)") (class "Default")
      (node (ref "H23") (pin "13") (pinfunction "13_13") (pintype "input"))
      (node (ref "H9") (pin "6") (pinfunction "6_6") (pintype "input"))
    )
    (net (code "138") (name "Net-(H23-Pad14)") (class "Default")
      (node (ref "H23") (pin "14") (pinfunction "14_14") (pintype "input"))
      (node (ref "H9") (pin "5") (pinfunction "5_5") (pintype "input"))
    )
    (net (code "139") (name "Net-(H23-Pad15)") (class "Default")
      (node (ref "H23") (pin "15") (pinfunction "15_15") (pintype "input"))
      (node (ref "H9") (pin "4") (pinfunction "4_4") (pintype "input"))
    )
    (net (code "140") (name "Net-(H23-Pad16)") (class "Default")
      (node (ref "H23") (pin "16") (pinfunction "16_16") (pintype "input"))
      (node (ref "H9") (pin "3") (pinfunction "3_3") (pintype "input"))
    )
    (net (code "141") (name "Net-(H23-Pad17)") (class "Default")
      (node (ref "H23") (pin "17") (pinfunction "17_17") (pintype "input"))
      (node (ref "H9") (pin "2") (pinfunction "2_2") (pintype "input"))
    )
    (net (code "142") (name "Net-(H23-Pad18)") (class "Default")
      (node (ref "H23") (pin "18") (pinfunction "18_18") (pintype "input"))
      (node (ref "H9") (pin "1") (pinfunction "1_1") (pintype "input"))
    )
  )
)
